# Balancing_Robot_1_1_Main.net
KiCad netlist of a schematic drawn in Altium Designer
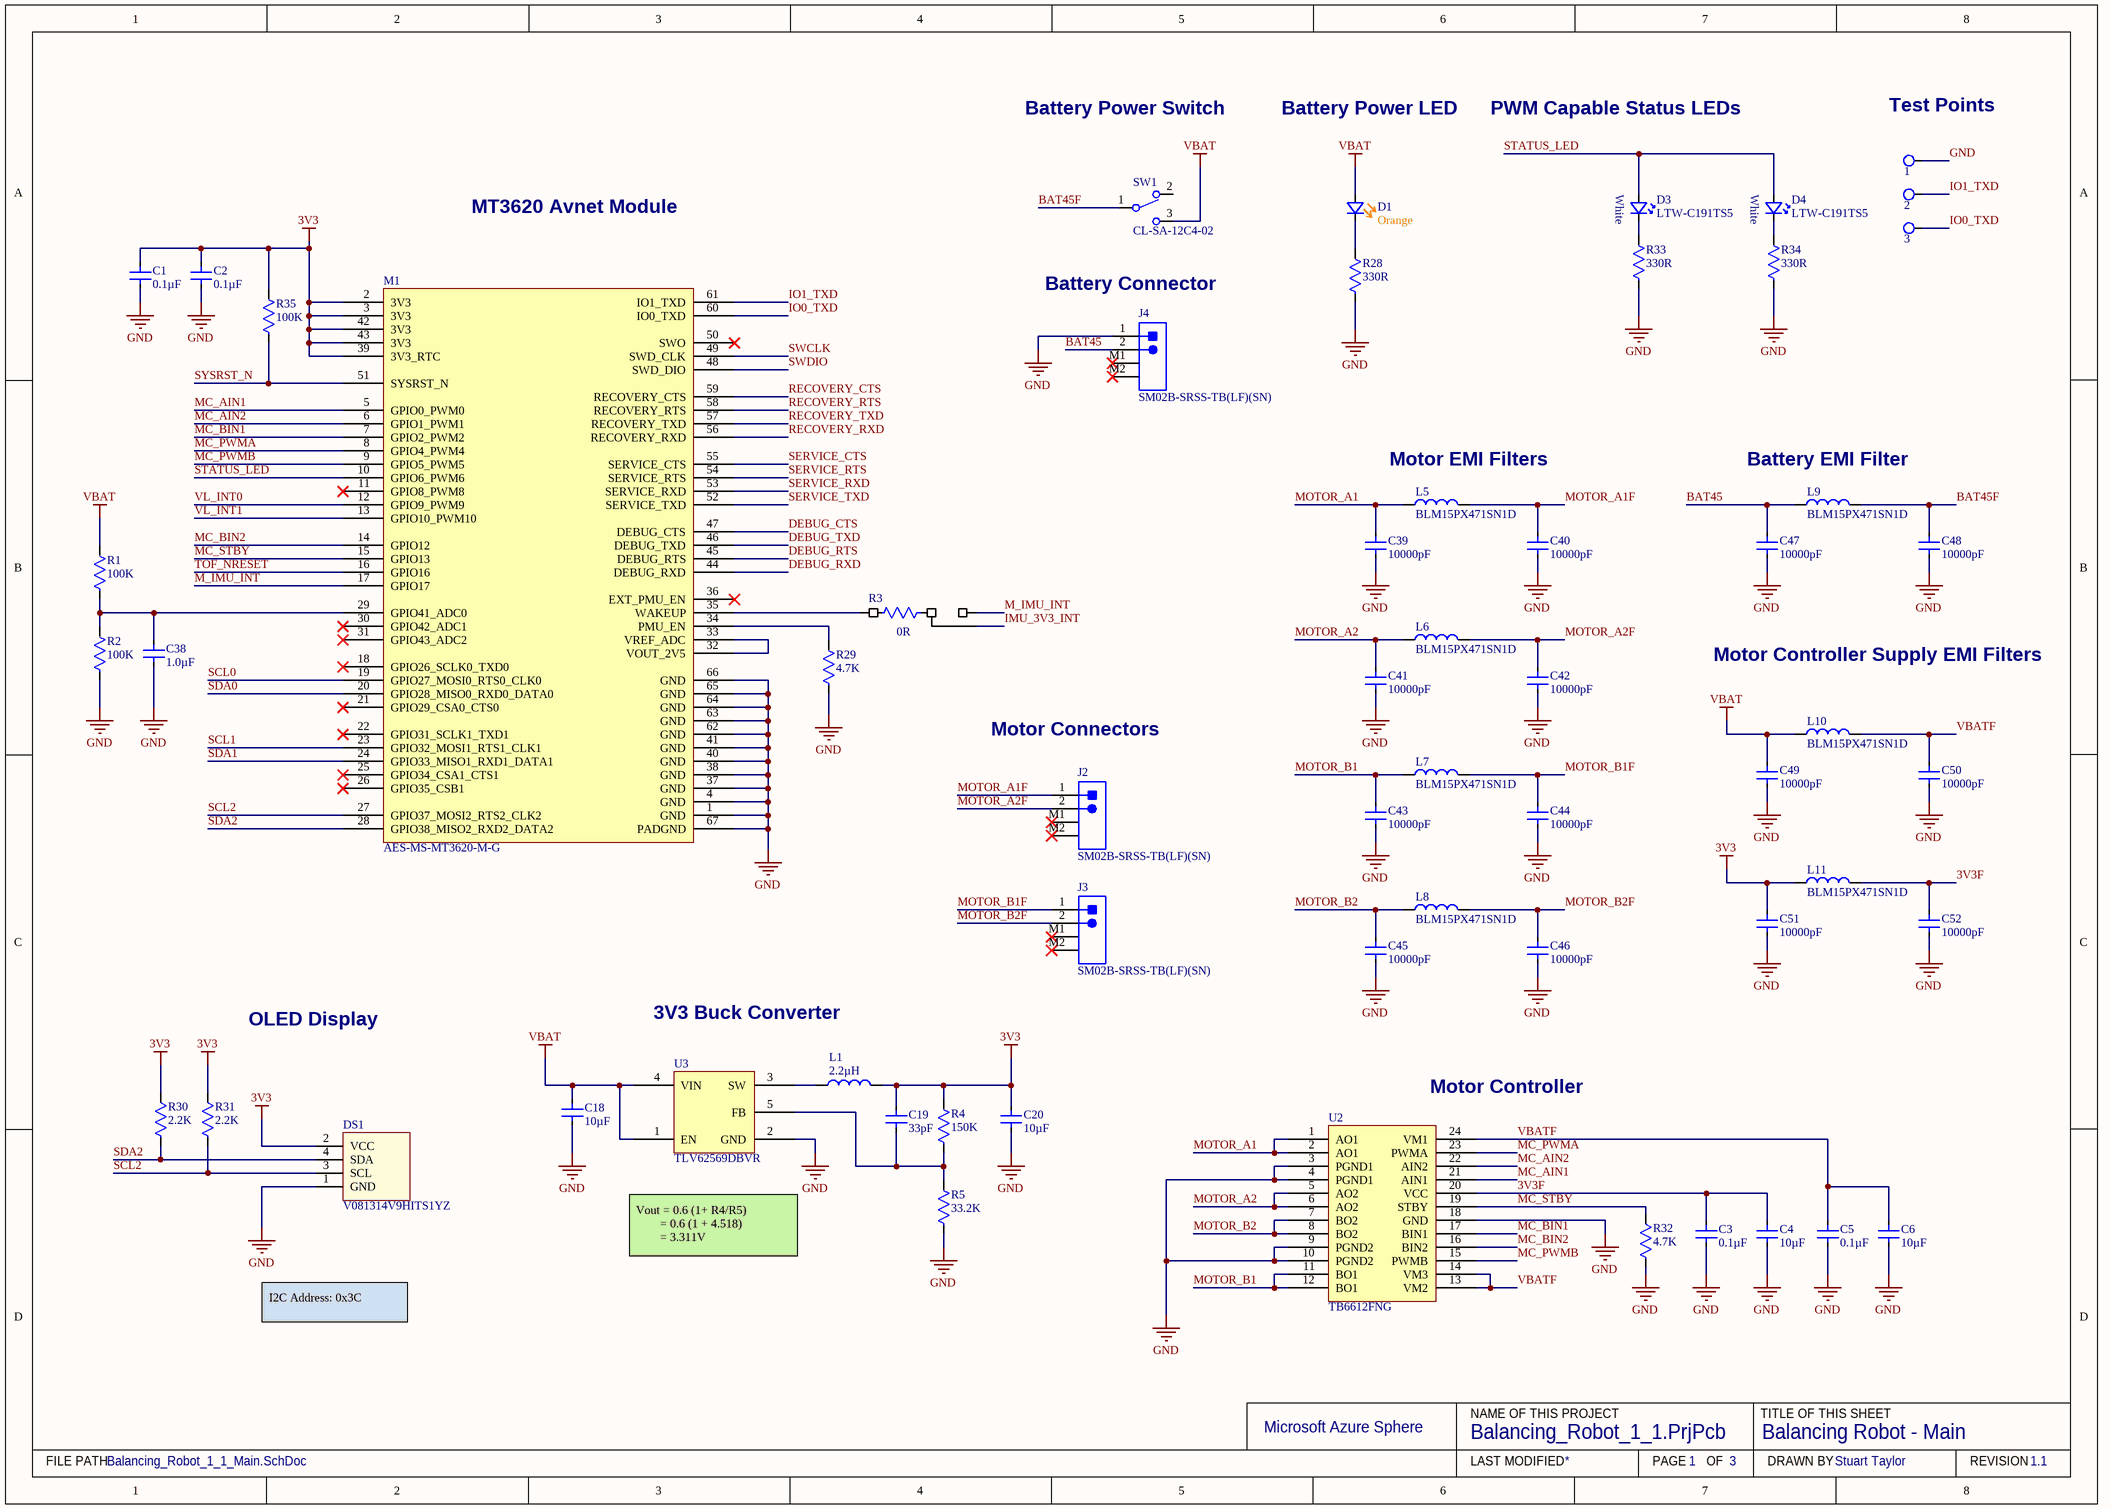
[diagram p0: Balancing_Robot_1_1_Main.SchDoc]

(export (version "E")
  (design (tool "Eeschema 10.0.6"))
  (components
    (comp (ref "1")
      (value "TestPoint")
      (footprint "Pad1.27mm")
      (description "Test Point")
      (libsource (lib "generic") (part "TestPoint"))
    )
    (comp (ref "2")
      (value "TestPoint")
      (footprint "Pad1.27mm")
      (description "Test Point")
      (libsource (lib "generic") (part "TestPoint"))
    )
    (comp (ref "3")
      (value "TestPoint")
      (footprint "Pad1.27mm")
      (description "Test Point")
      (libsource (lib "generic") (part "TestPoint"))
    )
    (comp (ref "C1")
      (value "0.1µF")
      (footprint "CAPC1005-EIA0402 0.55MM MED")
      (description "CAP CER 0.1UF 50V 10% X7R 0402")
      (fields
        (field (name "MANUFACTURER") "TDK Corporation")
        (field (name "MANUFACTURER PART NUMBER") "C1005X7R1H104K050BB")
        (field (name "CAPACITANCE") "0.1µF")
      )
      (libsource (lib "TDK_Capacitor_C_0402") (part "0.1µF 0402 X7R 50V"))
    )
    (comp (ref "C2")
      (value "0.1µF")
      (footprint "CAPC1005-EIA0402 0.55MM MED")
      (description "CAP CER 0.1UF 50V 10% X7R 0402")
      (fields
        (field (name "MANUFACTURER") "TDK Corporation")
        (field (name "MANUFACTURER PART NUMBER") "C1005X7R1H104K050BB")
        (field (name "CAPACITANCE") "0.1µF")
      )
      (libsource (lib "TDK_Capacitor_C_0402") (part "0.1µF 0402 X7R 50V"))
    )
    (comp (ref "C3")
      (value "0.1µF")
      (footprint "CAPC1005-EIA0402 0.55MM MED")
      (description "CAP CER 0.1UF 50V 10% X7R 0402")
      (fields
        (field (name "MANUFACTURER") "TDK Corporation")
        (field (name "MANUFACTURER PART NUMBER") "C1005X7R1H104K050BB")
        (field (name "CAPACITANCE") "0.1µF")
      )
      (libsource (lib "TDK_Capacitor_C_0402") (part "0.1µF 0402 X7R 50V"))
    )
    (comp (ref "C4")
      (value "10µF")
      (footprint "CAPC1005-EIA0402 0.55MM MED")
      (description "CAP CER 10UF 6.3V 20% X5R 0402")
      (fields
        (field (name "MANUFACTURER") "TDK Corporation")
        (field (name "MANUFACTURER PART NUMBER") "C1005X5R0J106M050BC")
        (field (name "CAPACITANCE") "10µF")
      )
      (libsource (lib "TDK_Capacitor_C_0402") (part "10µF 0402 X5R 6.3V"))
    )
    (comp (ref "C5")
      (value "0.1µF")
      (footprint "CAPC1005-EIA0402 0.55MM MED")
      (description "CAP CER 0.1UF 50V 10% X7R 0402")
      (fields
        (field (name "MANUFACTURER") "TDK Corporation")
        (field (name "MANUFACTURER PART NUMBER") "C1005X7R1H104K050BB")
        (field (name "CAPACITANCE") "0.1µF")
      )
      (libsource (lib "TDK_Capacitor_C_0402") (part "0.1µF 0402 X7R 50V"))
    )
    (comp (ref "C6")
      (value "10µF")
      (footprint "CAPC1005-EIA0402 0.55MM MED")
      (description "CAP CER 10UF 6.3V 20% X5R 0402")
      (fields
        (field (name "MANUFACTURER") "TDK Corporation")
        (field (name "MANUFACTURER PART NUMBER") "C1005X5R0J106M050BC")
        (field (name "CAPACITANCE") "10µF")
      )
      (libsource (lib "TDK_Capacitor_C_0402") (part "10µF 0402 X5R 6.3V"))
    )
    (comp (ref "C18")
      (value "10µF")
      (footprint "CAPC1608-EIA0603-1MM-MED")
      (description "CAP CER 10UF 25V 20% X5R 0603")
      (fields
        (field (name "MANUFACTURER") "TDK Corporation")
        (field (name "MANUFACTURER PART NUMBER") "C1608X5R1E106M080AC")
        (field (name "CAPACITANCE") "10µF")
      )
      (libsource (lib "TDK-Capacitor_C_0603") (part "10µF 0603 X5R 25V"))
    )
    (comp (ref "C19")
      (value "33pF")
      (footprint "CAPC1005-EIA0402 0.55MM MED")
      (description "CAP CER 33PF 50V 5% NP0 0402")
      (fields
        (field (name "MANUFACTURER") "TDK Corporation")
        (field (name "MANUFACTURER PART NUMBER") "C1005C0G1H330J050BA")
        (field (name "CAPACITANCE") "33pF")
      )
      (libsource (lib "TDK_Capacitor_C_0402") (part "33pF 0402 C0G, NP0 50V"))
    )
    (comp (ref "C20")
      (value "10µF")
      (footprint "CAPC1005-EIA0402 0.55MM MED")
      (description "CAP CER 10UF 6.3V 20% X5R 0402")
      (fields
        (field (name "MANUFACTURER") "TDK Corporation")
        (field (name "MANUFACTURER PART NUMBER") "C1005X5R0J106M050BC")
        (field (name "CAPACITANCE") "10µF")
      )
      (libsource (lib "TDK_Capacitor_C_0402") (part "10µF 0402 X5R 6.3V"))
    )
    (comp (ref "C38")
      (value "C1005X5R1V105K050BC")
      (footprint "CAPC1005-EIA0402 0.55MM MED")
      (description "CAP CER 1UF 35V 10% X5R 0402")
      (fields
        (field (name "MANUFACTURER") "TDK Corporation")
        (field (name "TOLERANCE") "±10%")
        (field (name "CAPACITANCE") "1.0µF")
      )
      (libsource (lib "TDK_Capacitor_C_0402") (part "1.0µF 0402 X5R 35V"))
    )
    (comp (ref "C39")
      (value "C1005X7R1H103K050BB")
      (footprint "CAPC1005-EIA0402 0.55MM MED")
      (description "CAP CER 10000PF 50V 10% X7R 0402")
      (fields
        (field (name "MANUFACTURER") "TDK Corporation")
        (field (name "TOLERANCE") "±10%")
        (field (name "CAPACITANCE") "10000pF")
      )
      (libsource (lib "TDK_Capacitor_C_0402") (part "10000pF 0402 X7R 50V"))
    )
    (comp (ref "C40")
      (value "C1005X7R1H103K050BB")
      (footprint "CAPC1005-EIA0402 0.55MM MED")
      (description "CAP CER 10000PF 50V 10% X7R 0402")
      (fields
        (field (name "MANUFACTURER") "TDK Corporation")
        (field (name "TOLERANCE") "±10%")
        (field (name "CAPACITANCE") "10000pF")
      )
      (libsource (lib "TDK_Capacitor_C_0402") (part "10000pF 0402 X7R 50V"))
    )
    (comp (ref "C41")
      (value "C1005X7R1H103K050BB")
      (footprint "CAPC1005-EIA0402 0.55MM MED")
      (description "CAP CER 10000PF 50V 10% X7R 0402")
      (fields
        (field (name "MANUFACTURER") "TDK Corporation")
        (field (name "TOLERANCE") "±10%")
        (field (name "CAPACITANCE") "10000pF")
      )
      (libsource (lib "TDK_Capacitor_C_0402") (part "10000pF 0402 X7R 50V"))
    )
    (comp (ref "C42")
      (value "C1005X7R1H103K050BB")
      (footprint "CAPC1005-EIA0402 0.55MM MED")
      (description "CAP CER 10000PF 50V 10% X7R 0402")
      (fields
        (field (name "MANUFACTURER") "TDK Corporation")
        (field (name "TOLERANCE") "±10%")
        (field (name "CAPACITANCE") "10000pF")
      )
      (libsource (lib "TDK_Capacitor_C_0402") (part "10000pF 0402 X7R 50V"))
    )
    (comp (ref "C43")
      (value "C1005X7R1H103K050BB")
      (footprint "CAPC1005-EIA0402 0.55MM MED")
      (description "CAP CER 10000PF 50V 10% X7R 0402")
      (fields
        (field (name "MANUFACTURER") "TDK Corporation")
        (field (name "TOLERANCE") "±10%")
        (field (name "CAPACITANCE") "10000pF")
      )
      (libsource (lib "TDK_Capacitor_C_0402") (part "10000pF 0402 X7R 50V"))
    )
    (comp (ref "C44")
      (value "C1005X7R1H103K050BB")
      (footprint "CAPC1005-EIA0402 0.55MM MED")
      (description "CAP CER 10000PF 50V 10% X7R 0402")
      (fields
        (field (name "MANUFACTURER") "TDK Corporation")
        (field (name "TOLERANCE") "±10%")
        (field (name "CAPACITANCE") "10000pF")
      )
      (libsource (lib "TDK_Capacitor_C_0402") (part "10000pF 0402 X7R 50V"))
    )
    (comp (ref "C45")
      (value "C1005X7R1H103K050BB")
      (footprint "CAPC1005-EIA0402 0.55MM MED")
      (description "CAP CER 10000PF 50V 10% X7R 0402")
      (fields
        (field (name "MANUFACTURER") "TDK Corporation")
        (field (name "TOLERANCE") "±10%")
        (field (name "CAPACITANCE") "10000pF")
      )
      (libsource (lib "TDK_Capacitor_C_0402") (part "10000pF 0402 X7R 50V"))
    )
    (comp (ref "C46")
      (value "C1005X7R1H103K050BB")
      (footprint "CAPC1005-EIA0402 0.55MM MED")
      (description "CAP CER 10000PF 50V 10% X7R 0402")
      (fields
        (field (name "MANUFACTURER") "TDK Corporation")
        (field (name "TOLERANCE") "±10%")
        (field (name "CAPACITANCE") "10000pF")
      )
      (libsource (lib "TDK_Capacitor_C_0402") (part "10000pF 0402 X7R 50V"))
    )
    (comp (ref "C47")
      (value "C1005X7R1H103K050BB")
      (footprint "CAPC1005-EIA0402 0.55MM MED")
      (description "CAP CER 10000PF 50V 10% X7R 0402")
      (fields
        (field (name "MANUFACTURER") "TDK Corporation")
        (field (name "TOLERANCE") "±10%")
        (field (name "CAPACITANCE") "10000pF")
      )
      (libsource (lib "TDK_Capacitor_C_0402") (part "10000pF 0402 X7R 50V"))
    )
    (comp (ref "C48")
      (value "C1005X7R1H103K050BB")
      (footprint "CAPC1005-EIA0402 0.55MM MED")
      (description "CAP CER 10000PF 50V 10% X7R 0402")
      (fields
        (field (name "MANUFACTURER") "TDK Corporation")
        (field (name "TOLERANCE") "±10%")
        (field (name "CAPACITANCE") "10000pF")
      )
      (libsource (lib "TDK_Capacitor_C_0402") (part "10000pF 0402 X7R 50V"))
    )
    (comp (ref "C49")
      (value "C1005X7R1H103K050BB")
      (footprint "CAPC1005-EIA0402 0.55MM MED")
      (description "CAP CER 10000PF 50V 10% X7R 0402")
      (fields
        (field (name "MANUFACTURER") "TDK Corporation")
        (field (name "TOLERANCE") "±10%")
        (field (name "CAPACITANCE") "10000pF")
      )
      (libsource (lib "TDK_Capacitor_C_0402") (part "10000pF 0402 X7R 50V"))
    )
    (comp (ref "C50")
      (value "C1005X7R1H103K050BB")
      (footprint "CAPC1005-EIA0402 0.55MM MED")
      (description "CAP CER 10000PF 50V 10% X7R 0402")
      (fields
        (field (name "MANUFACTURER") "TDK Corporation")
        (field (name "TOLERANCE") "±10%")
        (field (name "CAPACITANCE") "10000pF")
      )
      (libsource (lib "TDK_Capacitor_C_0402") (part "10000pF 0402 X7R 50V"))
    )
    (comp (ref "C51")
      (value "C1005X7R1H103K050BB")
      (footprint "CAPC1005-EIA0402 0.55MM MED")
      (description "CAP CER 10000PF 50V 10% X7R 0402")
      (fields
        (field (name "MANUFACTURER") "TDK Corporation")
        (field (name "TOLERANCE") "±10%")
        (field (name "CAPACITANCE") "10000pF")
      )
      (libsource (lib "TDK_Capacitor_C_0402") (part "10000pF 0402 X7R 50V"))
    )
    (comp (ref "C52")
      (value "C1005X7R1H103K050BB")
      (footprint "CAPC1005-EIA0402 0.55MM MED")
      (description "CAP CER 10000PF 50V 10% X7R 0402")
      (fields
        (field (name "MANUFACTURER") "TDK Corporation")
        (field (name "TOLERANCE") "±10%")
        (field (name "CAPACITANCE") "10000pF")
      )
      (libsource (lib "TDK_Capacitor_C_0402") (part "10000pF 0402 X7R 50V"))
    )
    (comp (ref "D1")
      (value "SML-D12D")
      (footprint "Rohm SML-D12 Orange")
      (description "1.6 x 0.8 x 0.55mm (0603) LED 605nm Orange")
      (fields
        (field (name "MANUFACTURER") "Rohm Semiconductor")
        (field (name "MANUFACTURER PART NUMBER") "SML-D12D8WT86")
        (field (name "COLOUR") "Orange")
      )
      (libsource (lib "Rohm") (part "SML-D12D"))
    )
    (comp (ref "D3")
      (value "LTW-C191TS5")
      (footprint "LTW-C191TS5")
      (description "LED Uni-Color White 2-Pin Chip LED T/R")
      (fields (field (name "MANUFACTURER") "Vishay Lite-On"))
      (libsource (lib "Lite-On") (part "LTW-C191TS5"))
    )
    (comp (ref "D4")
      (value "LTW-C191TS5")
      (footprint "LTW-C191TS5")
      (description "LED Uni-Color White 2-Pin Chip LED T/R")
      (fields (field (name "MANUFACTURER") "Vishay Lite-On"))
      (libsource (lib "Lite-On") (part "LTW-C191TS5"))
    )
    (comp (ref "DS1")
      (value "V081314V9HITS1YZ")
      (footprint "Long_Display")
      (libsource (lib "MakerHawk") (part "V081314V9HITS1YZ"))
    )
    (comp (ref "J2")
      (value "SM02B-SRSS-TB(LF)(SN)")
      (footprint "SM02B-SRSS-TB")
      (description "Conn Shrouded Header HDR 2 POS 1mm Solder RA SMD T/R")
      (fields (field (name "MANUFACTURER") "JST"))
      (libsource (lib "JST") (part "SM02B-SRSS-TB(LF)(SN)"))
    )
    (comp (ref "J3")
      (value "SM02B-SRSS-TB(LF)(SN)")
      (footprint "SM02B-SRSS-TB")
      (description "Conn Shrouded Header HDR 2 POS 1mm Solder RA SMD T/R")
      (fields (field (name "MANUFACTURER") "JST"))
      (libsource (lib "JST") (part "SM02B-SRSS-TB(LF)(SN)"))
    )
    (comp (ref "J4")
      (value "SM02B-SRSS-TB(LF)(SN)")
      (footprint "SM02B-SRSS-TB")
      (description "Conn Shrouded Header HDR 2 POS 1mm Solder RA SMD T/R")
      (fields (field (name "MANUFACTURER") "JST"))
      (libsource (lib "JST") (part "SM02B-SRSS-TB(LF)(SN)"))
    )
    (comp (ref "L1")
      (value "2.2µH")
      (footprint "NR3015T2R2M")
      (description "FIXED IND 2.2UH 1.5A 72 MOHM SMD")
      (fields
        (field (name "MANUFACTURER") "Taiyo Yuden")
        (field (name "MANUFACTURER PART NUMBER") "NR3015T2R2M")
      )
      (libsource (lib "TaiyoYuden ") (part "NR3015T2R2M"))
    )
    (comp (ref "L5")
      (value "BLM15PX471SN1D")
      (footprint "Generic Ferrite 0402")
      (description "Murata")
      (fields (field (name "TOLERANCE") "25%"))
      (libsource (lib "Murata") (part "BLM15PX471SN1D"))
    )
    (comp (ref "L6")
      (value "BLM15PX471SN1D")
      (footprint "Generic Ferrite 0402")
      (description "Murata")
      (fields (field (name "TOLERANCE") "25%"))
      (libsource (lib "Murata") (part "BLM15PX471SN1D"))
    )
    (comp (ref "L7")
      (value "BLM15PX471SN1D")
      (footprint "Generic Ferrite 0402")
      (description "Murata")
      (fields (field (name "TOLERANCE") "25%"))
      (libsource (lib "Murata") (part "BLM15PX471SN1D"))
    )
    (comp (ref "L8")
      (value "BLM15PX471SN1D")
      (footprint "Generic Ferrite 0402")
      (description "Murata")
      (fields (field (name "TOLERANCE") "25%"))
      (libsource (lib "Murata") (part "BLM15PX471SN1D"))
    )
    (comp (ref "L9")
      (value "BLM15PX471SN1D")
      (footprint "Generic Ferrite 0402")
      (description "Murata")
      (fields (field (name "TOLERANCE") "25%"))
      (libsource (lib "Murata") (part "BLM15PX471SN1D"))
    )
    (comp (ref "L10")
      (value "BLM15PX471SN1D")
      (footprint "Generic Ferrite 0402")
      (description "Murata")
      (fields (field (name "TOLERANCE") "25%"))
      (libsource (lib "Murata") (part "BLM15PX471SN1D"))
    )
    (comp (ref "L11")
      (value "BLM15PX471SN1D")
      (footprint "Generic Ferrite 0402")
      (description "Murata")
      (fields (field (name "TOLERANCE") "25%"))
      (libsource (lib "Murata") (part "BLM15PX471SN1D"))
    )
    (comp (ref "M1")
      (value "AES-MS-MT3620-M-G")
      (footprint "AES-MS-MT3620-M-G")
      (libsource (lib "Avnet") (part "AES-MS-MT3620-M-G (SAT)"))
    )
    (comp (ref "R1")
      (value "100K")
      (footprint "RES 0402 MEDIUM DENSITY")
      (description "RES 100K OHM 1/10W 1% 0402 SMD")
      (fields
        (field (name "MANUFACTURER") "Panasonic Electronic Components")
        (field (name "MANUFACTURER PART NUMBER") "ERJ-2RKF1003X")
        (field (name "RESISTANCE (OHMS)") "100K")
      )
      (libsource (lib "Panasonic_Resistor_ERJ2R") (part "100K"))
    )
    (comp (ref "R2")
      (value "100K")
      (footprint "RES 0402 MEDIUM DENSITY")
      (description "RES 100K OHM 1/10W 1% 0402 SMD")
      (fields
        (field (name "MANUFACTURER") "Panasonic Electronic Components")
        (field (name "MANUFACTURER PART NUMBER") "ERJ-2RKF1003X")
        (field (name "RESISTANCE (OHMS)") "100K")
      )
      (libsource (lib "Panasonic_Resistor_ERJ2R") (part "100K"))
    )
    (comp (ref "R3")
      (value "0R")
      (footprint "THREE-WAY-0402-NO-SHORT")
      (description "RES SMD 0.0OHM JUMPER 1/10W 0402")
      (fields
        (field (name "MANUFACTURER") "Panasonic Electronic Components")
        (field (name "MANUFACTURER PART NUMBER") "ERJ-2GE0R00X")
      )
      (libsource (lib "generic-res") (part "THREE-WAY-0R-0402-NO-SHORT"))
    )
    (comp (ref "R4")
      (value "150K")
      (footprint "RES 0402 MEDIUM DENSITY")
      (description "RES 150K OHM 1/10W 1% 0402 SMD")
      (fields
        (field (name "MANUFACTURER") "Panasonic Electronic Components")
        (field (name "MANUFACTURER PART NUMBER") "ERJ-2RKF1503X")
        (field (name "RESISTANCE (OHMS)") "150K")
      )
      (libsource (lib "Panasonic_Resistor_ERJ2R") (part "150K"))
    )
    (comp (ref "R5")
      (value "33.2K")
      (footprint "RES 0402 MEDIUM DENSITY")
      (description "RES 33.2K OHM 1/10W 1% 0402 SMD")
      (fields
        (field (name "MANUFACTURER") "Panasonic Electronic Components")
        (field (name "MANUFACTURER PART NUMBER") "ERJ-2RKF3322X")
        (field (name "RESISTANCE (OHMS)") "33.2K")
      )
      (libsource (lib "Panasonic_Resistor_ERJ2R") (part "33.2K"))
    )
    (comp (ref "R28")
      (value "330R")
      (footprint "RES 0402 MEDIUM DENSITY")
      (description "RES 330 OHM 1/10W 1% 0402 SMD")
      (fields
        (field (name "MANUFACTURER") "Panasonic Electronic Components")
        (field (name "MANUFACTURER PART NUMBER") "ERJ-2RKF3300X")
        (field (name "RESISTANCE (OHMS)") "330R")
      )
      (libsource (lib "Panasonic_Resistor_ERJ2R") (part "330R"))
    )
    (comp (ref "R29")
      (value "4.7K")
      (footprint "RES 0402 MEDIUM DENSITY")
      (description "RES 4.7K OHM 1/10W 1% 0402 SMD")
      (fields
        (field (name "MANUFACTURER") "Panasonic Electronic Components")
        (field (name "MANUFACTURER PART NUMBER") "ERJ-2RKF4701X")
        (field (name "RESISTANCE (OHMS)") "4.7K")
      )
      (libsource (lib "Panasonic_Resistor_ERJ2R") (part "4.7K"))
    )
    (comp (ref "R30")
      (value "2.2K")
      (footprint "RES 0402 MEDIUM DENSITY")
      (description "RES 2.2K OHM 1/10W 1% 0402 SMD")
      (fields
        (field (name "MANUFACTURER") "Panasonic Electronic Components")
        (field (name "MANUFACTURER PART NUMBER") "ERJ-2RKF2201X")
        (field (name "RESISTANCE (OHMS)") "2.2K")
      )
      (libsource (lib "Panasonic_Resistor_ERJ2R") (part "2.2K"))
    )
    (comp (ref "R31")
      (value "2.2K")
      (footprint "RES 0402 MEDIUM DENSITY")
      (description "RES 2.2K OHM 1/10W 1% 0402 SMD")
      (fields
        (field (name "MANUFACTURER") "Panasonic Electronic Components")
        (field (name "MANUFACTURER PART NUMBER") "ERJ-2RKF2201X")
        (field (name "RESISTANCE (OHMS)") "2.2K")
      )
      (libsource (lib "Panasonic_Resistor_ERJ2R") (part "2.2K"))
    )
    (comp (ref "R32")
      (value "4.7K")
      (footprint "RES 0402 MEDIUM DENSITY")
      (description "RES 4.7K OHM 1/10W 1% 0402 SMD")
      (fields
        (field (name "MANUFACTURER") "Panasonic Electronic Components")
        (field (name "MANUFACTURER PART NUMBER") "ERJ-2RKF4701X")
        (field (name "RESISTANCE (OHMS)") "4.7K")
      )
      (libsource (lib "Panasonic_Resistor_ERJ2R") (part "4.7K"))
    )
    (comp (ref "R33")
      (value "330R")
      (footprint "RES 0402 MEDIUM DENSITY")
      (description "RES 330 OHM 1/10W 1% 0402 SMD")
      (fields
        (field (name "MANUFACTURER") "Panasonic Electronic Components")
        (field (name "MANUFACTURER PART NUMBER") "ERJ-2RKF3300X")
        (field (name "RESISTANCE (OHMS)") "330R")
      )
      (libsource (lib "Panasonic_Resistor_ERJ2R") (part "330R"))
    )
    (comp (ref "R34")
      (value "330R")
      (footprint "RES 0402 MEDIUM DENSITY")
      (description "RES 330 OHM 1/10W 1% 0402 SMD")
      (fields
        (field (name "MANUFACTURER") "Panasonic Electronic Components")
        (field (name "MANUFACTURER PART NUMBER") "ERJ-2RKF3300X")
        (field (name "RESISTANCE (OHMS)") "330R")
      )
      (libsource (lib "Panasonic_Resistor_ERJ2R") (part "330R"))
    )
    (comp (ref "R35")
      (value "100K")
      (footprint "RES 0402 MEDIUM DENSITY")
      (description "RES 100K OHM 1/10W 1% 0402 SMD")
      (fields
        (field (name "MANUFACTURER") "Panasonic Electronic Components")
        (field (name "MANUFACTURER PART NUMBER") "ERJ-2RKF1003X")
        (field (name "RESISTANCE (OHMS)") "100K")
      )
      (libsource (lib "Panasonic_Resistor_ERJ2R") (part "100K"))
    )
    (comp (ref "SW1")
      (value "CL-SA-12C4-02")
      (footprint "CL-SA-12C4-02")
      (description "SWITCH SLIDE SPDT 500MA 12V")
      (fields (field (name "MANUFACTURER") "Nidec Copal"))
      (libsource (lib "Copal") (part "CL-SA-12C4-02"))
    )
    (comp (ref "U2")
      (value "TB6612FNG")
      (footprint "TB6612FNG")
      (description "DC Motor Driver 3V 24-Pin SSOP T/R")
      (fields
        (field (name "MANUFACTURER") "Toshiba")
        (field (name "MANUFACTURER PART NUMBER") "TB6612FNG,C,8,EL")
      )
      (libsource (lib "Toshiba") (part "TB6612FNG"))
    )
    (comp (ref "U3")
      (value "TLV62569DBVR")
      (footprint "TI-SOT23-6")
      (description "Variable voltage buck converter")
      (fields (field (name "MANUFACTURER") "Texas Instruments"))
      (libsource (lib "TexasInstruments") (part "TLV62569DBVR"))
    )
  )
  (nets
    (net (code "1") (name "/3V3F") (class "Default")
      (node (ref "C3") (pin "2") (pinfunction "2_2") (pintype "passive"))
      (node (ref "C4") (pin "2") (pinfunction "2_2") (pintype "passive"))
      (node (ref "C52") (pin "2") (pinfunction "2_2") (pintype "passive"))
      (node (ref "L11") (pin "2") (pinfunction "2_2") (pintype "passive"))
      (node (ref "U2") (pin "20") (pinfunction "VCC_20") (pintype "passive"))
    )
    (net (code "2") (name "/BAT45") (class "Default")
      (node (ref "C47") (pin "2") (pinfunction "2_2") (pintype "passive"))
      (node (ref "J4") (pin "2") (pinfunction "2_2") (pintype "passive"))
      (node (ref "L9") (pin "1") (pinfunction "1_1") (pintype "passive"))
    )
    (net (code "3") (name "/BAT45F") (class "Default")
      (node (ref "C48") (pin "2") (pinfunction "2_2") (pintype "passive"))
      (node (ref "L9") (pin "2") (pinfunction "2_2") (pintype "passive"))
      (node (ref "SW1") (pin "1") (pinfunction "1_1") (pintype "passive"))
    )
    (net (code "4") (name "/DEBUG_CTS") (class "Default")
      (node (ref "M1") (pin "47") (pinfunction "DEBUG_CTS_47") (pintype "passive"))
    )
    (net (code "5") (name "/DEBUG_RTS") (class "Default")
      (node (ref "M1") (pin "45") (pinfunction "DEBUG_RTS_45") (pintype "passive"))
    )
    (net (code "6") (name "/DEBUG_RXD") (class "Default")
      (node (ref "M1") (pin "44") (pinfunction "DEBUG_RXD_44") (pintype "passive"))
    )
    (net (code "7") (name "/DEBUG_TXD") (class "Default")
      (node (ref "M1") (pin "46") (pinfunction "DEBUG_TXD_46") (pintype "passive"))
    )
    (net (code "8") (name "/IMU_3V3_INT") (class "Default")
      (node (ref "R3") (pin "2") (pinfunction "2_2") (pintype "passive"))
    )
    (net (code "9") (name "/IO0_TXD") (class "Default")
      (node (ref "3") (pin "1") (pinfunction "1_1") (pintype "passive"))
      (node (ref "M1") (pin "60") (pinfunction "IO0_TXD_60") (pintype "passive"))
    )
    (net (code "10") (name "/IO1_TXD") (class "Default")
      (node (ref "2") (pin "1") (pinfunction "1_1") (pintype "passive"))
      (node (ref "M1") (pin "61") (pinfunction "IO1_TXD_61") (pintype "passive"))
    )
    (net (code "11") (name "/MC_AIN1") (class "Default")
      (node (ref "M1") (pin "5") (pinfunction "GPIO0_PWM0_5") (pintype "passive"))
      (node (ref "U2") (pin "21") (pinfunction "AIN1_21") (pintype "passive"))
    )
    (net (code "12") (name "/MC_AIN2") (class "Default")
      (node (ref "M1") (pin "6") (pinfunction "GPIO1_PWM1_6") (pintype "passive"))
      (node (ref "U2") (pin "22") (pinfunction "AIN2_22") (pintype "passive"))
    )
    (net (code "13") (name "/MC_BIN1") (class "Default")
      (node (ref "M1") (pin "7") (pinfunction "GPIO2_PWM2_7") (pintype "passive"))
      (node (ref "U2") (pin "17") (pinfunction "BIN1_17") (pintype "passive"))
    )
    (net (code "14") (name "/MC_BIN2") (class "Default")
      (node (ref "M1") (pin "14") (pinfunction "GPIO12_14") (pintype "passive"))
      (node (ref "U2") (pin "16") (pinfunction "BIN2_16") (pintype "passive"))
    )
    (net (code "15") (name "/MC_PWMA") (class "Default")
      (node (ref "M1") (pin "8") (pinfunction "GPIO4_PWM4_8") (pintype "passive"))
      (node (ref "U2") (pin "23") (pinfunction "PWMA_23") (pintype "passive"))
    )
    (net (code "16") (name "/MC_PWMB") (class "Default")
      (node (ref "M1") (pin "9") (pinfunction "GPIO5_PWM5_9") (pintype "passive"))
      (node (ref "U2") (pin "15") (pinfunction "PWMB_15") (pintype "passive"))
    )
    (net (code "17") (name "/MC_STBY") (class "Default")
      (node (ref "M1") (pin "15") (pinfunction "GPIO13_15") (pintype "passive"))
      (node (ref "R32") (pin "1") (pinfunction "1_1") (pintype "passive"))
      (node (ref "U2") (pin "19") (pinfunction "STBY_19") (pintype "passive"))
    )
    (net (code "18") (name "/MOTOR_A1") (class "Default")
      (node (ref "C39") (pin "2") (pinfunction "2_2") (pintype "passive"))
      (node (ref "L5") (pin "1") (pinfunction "1_1") (pintype "passive"))
      (node (ref "U2") (pin "1") (pinfunction "AO1_1") (pintype "passive"))
      (node (ref "U2") (pin "2") (pinfunction "AO1_2") (pintype "passive"))
    )
    (net (code "19") (name "/MOTOR_A1F") (class "Default")
      (node (ref "C40") (pin "2") (pinfunction "2_2") (pintype "passive"))
      (node (ref "J2") (pin "1") (pinfunction "1_1") (pintype "passive"))
      (node (ref "L5") (pin "2") (pinfunction "2_2") (pintype "passive"))
    )
    (net (code "20") (name "/MOTOR_A2") (class "Default")
      (node (ref "C41") (pin "2") (pinfunction "2_2") (pintype "passive"))
      (node (ref "L6") (pin "1") (pinfunction "1_1") (pintype "passive"))
      (node (ref "U2") (pin "5") (pinfunction "AO2_5") (pintype "passive"))
      (node (ref "U2") (pin "6") (pinfunction "AO2_6") (pintype "passive"))
    )
    (net (code "21") (name "/MOTOR_A2F") (class "Default")
      (node (ref "C42") (pin "2") (pinfunction "2_2") (pintype "passive"))
      (node (ref "J2") (pin "2") (pinfunction "2_2") (pintype "passive"))
      (node (ref "L6") (pin "2") (pinfunction "2_2") (pintype "passive"))
    )
    (net (code "22") (name "/MOTOR_B1") (class "Default")
      (node (ref "C43") (pin "2") (pinfunction "2_2") (pintype "passive"))
      (node (ref "L7") (pin "1") (pinfunction "1_1") (pintype "passive"))
      (node (ref "U2") (pin "11") (pinfunction "BO1_11") (pintype "passive"))
      (node (ref "U2") (pin "12") (pinfunction "BO1_12") (pintype "passive"))
    )
    (net (code "23") (name "/MOTOR_B1F") (class "Default")
      (node (ref "C44") (pin "2") (pinfunction "2_2") (pintype "passive"))
      (node (ref "J3") (pin "1") (pinfunction "1_1") (pintype "passive"))
      (node (ref "L7") (pin "2") (pinfunction "2_2") (pintype "passive"))
    )
    (net (code "24") (name "/MOTOR_B2") (class "Default")
      (node (ref "C45") (pin "2") (pinfunction "2_2") (pintype "passive"))
      (node (ref "L8") (pin "1") (pinfunction "1_1") (pintype "passive"))
      (node (ref "U2") (pin "7") (pinfunction "BO2_7") (pintype "passive"))
      (node (ref "U2") (pin "8") (pinfunction "BO2_8") (pintype "passive"))
    )
    (net (code "25") (name "/MOTOR_B2F") (class "Default")
      (node (ref "C46") (pin "2") (pinfunction "2_2") (pintype "passive"))
      (node (ref "J3") (pin "2") (pinfunction "2_2") (pintype "passive"))
      (node (ref "L8") (pin "2") (pinfunction "2_2") (pintype "passive"))
    )
    (net (code "26") (name "/M_IMU_INT") (class "Default")
      (node (ref "M1") (pin "17") (pinfunction "GPIO17_17") (pintype "passive"))
      (node (ref "R3") (pin "3") (pinfunction "3_3") (pintype "passive"))
    )
    (net (code "27") (name "/RECOVERY_CTS") (class "Default")
      (node (ref "M1") (pin "59") (pinfunction "RECOVERY_CTS_59") (pintype "passive"))
    )
    (net (code "28") (name "/RECOVERY_RTS") (class "Default")
      (node (ref "M1") (pin "58") (pinfunction "RECOVERY_RTS_58") (pintype "passive"))
    )
    (net (code "29") (name "/RECOVERY_RXD") (class "Default")
      (node (ref "M1") (pin "56") (pinfunction "RECOVERY_RXD_56") (pintype "passive"))
    )
    (net (code "30") (name "/RECOVERY_TXD") (class "Default")
      (node (ref "M1") (pin "57") (pinfunction "RECOVERY_TXD_57") (pintype "passive"))
    )
    (net (code "31") (name "/SCL0") (class "Default")
      (node (ref "M1") (pin "19") (pinfunction "GPIO27_MOSI0_RTS0_CLK0_19") (pintype "passive"))
    )
    (net (code "32") (name "/SCL1") (class "Default")
      (node (ref "M1") (pin "23") (pinfunction "GPIO32_MOSI1_RTS1_CLK1_23") (pintype "passive"))
    )
    (net (code "33") (name "/SCL2") (class "Default")
      (node (ref "DS1") (pin "3") (pinfunction "SCL_3") (pintype "passive"))
      (node (ref "M1") (pin "27") (pinfunction "GPIO37_MOSI2_RTS2_CLK2_27") (pintype "passive"))
      (node (ref "R31") (pin "2") (pinfunction "2_2") (pintype "passive"))
    )
    (net (code "34") (name "/SDA0") (class "Default")
      (node (ref "M1") (pin "20") (pinfunction "GPIO28_MISO0_RXD0_DATA0_20") (pintype "passive"))
    )
    (net (code "35") (name "/SDA1") (class "Default")
      (node (ref "M1") (pin "24") (pinfunction "GPIO33_MISO1_RXD1_DATA1_24") (pintype "passive"))
    )
    (net (code "36") (name "/SDA2") (class "Default")
      (node (ref "DS1") (pin "4") (pinfunction "SDA_4") (pintype "passive"))
      (node (ref "M1") (pin "28") (pinfunction "GPIO38_MISO2_RXD2_DATA2_28") (pintype "passive"))
      (node (ref "R30") (pin "2") (pinfunction "2_2") (pintype "passive"))
    )
    (net (code "37") (name "/SERVICE_CTS") (class "Default")
      (node (ref "M1") (pin "55") (pinfunction "SERVICE_CTS_55") (pintype "passive"))
    )
    (net (code "38") (name "/SERVICE_RTS") (class "Default")
      (node (ref "M1") (pin "54") (pinfunction "SERVICE_RTS_54") (pintype "passive"))
    )
    (net (code "39") (name "/SERVICE_RXD") (class "Default")
      (node (ref "M1") (pin "53") (pinfunction "SERVICE_RXD_53") (pintype "passive"))
    )
    (net (code "40") (name "/SERVICE_TXD") (class "Default")
      (node (ref "M1") (pin "52") (pinfunction "SERVICE_TXD_52") (pintype "passive"))
    )
    (net (code "41") (name "/STATUS_LED") (class "Default")
      (node (ref "D3") (pin "2") (pinfunction "A_2") (pintype "passive"))
      (node (ref "D4") (pin "2") (pinfunction "A_2") (pintype "passive"))
      (node (ref "M1") (pin "10") (pinfunction "GPIO6_PWM6_10") (pintype "passive"))
    )
    (net (code "42") (name "/SWCLK") (class "Default")
      (node (ref "M1") (pin "49") (pinfunction "SWD_CLK_49") (pintype "passive"))
    )
    (net (code "43") (name "/SWDIO") (class "Default")
      (node (ref "M1") (pin "48") (pinfunction "SWD_DIO_48") (pintype "passive"))
    )
    (net (code "44") (name "/SYSRST_N") (class "Default")
      (node (ref "M1") (pin "51") (pinfunction "SYSRST_N_51") (pintype "passive"))
      (node (ref "R35") (pin "2") (pinfunction "2_2") (pintype "passive"))
    )
    (net (code "45") (name "/TOF_NRESET") (class "Default")
      (node (ref "M1") (pin "16") (pinfunction "GPIO16_16") (pintype "passive"))
    )
    (net (code "46") (name "/VBATF") (class "Default")
      (node (ref "C5") (pin "2") (pinfunction "2_2") (pintype "passive"))
      (node (ref "C50") (pin "2") (pinfunction "2_2") (pintype "passive"))
      (node (ref "C6") (pin "2") (pinfunction "2_2") (pintype "passive"))
      (node (ref "L10") (pin "2") (pinfunction "2_2") (pintype "passive"))
      (node (ref "U2") (pin "13") (pinfunction "VM2_13") (pintype "passive"))
      (node (ref "U2") (pin "14") (pinfunction "VM3_14") (pintype "passive"))
      (node (ref "U2") (pin "24") (pinfunction "VM1_24") (pintype "passive"))
    )
    (net (code "47") (name "/VL_INT0") (class "Default")
      (node (ref "M1") (pin "12") (pinfunction "GPIO9_PWM9_12") (pintype "passive"))
    )
    (net (code "48") (name "/VL_INT1") (class "Default")
      (node (ref "M1") (pin "13") (pinfunction "GPIO10_PWM10_13") (pintype "passive"))
    )
    (net (code "49") (name "3V3") (class "Default")
      (node (ref "C1") (pin "2") (pinfunction "2_2") (pintype "passive"))
      (node (ref "C19") (pin "2") (pinfunction "2_2") (pintype "passive"))
      (node (ref "C2") (pin "2") (pinfunction "2_2") (pintype "passive"))
      (node (ref "C20") (pin "2") (pinfunction "2_2") (pintype "passive"))
      (node (ref "C51") (pin "2") (pinfunction "2_2") (pintype "passive"))
      (node (ref "DS1") (pin "2") (pinfunction "VCC_2") (pintype "passive"))
      (node (ref "L1") (pin "2") (pinfunction "2_2") (pintype "passive"))
      (node (ref "L11") (pin "1") (pinfunction "1_1") (pintype "passive"))
      (node (ref "M1") (pin "2") (pinfunction "3V3_2") (pintype "passive"))
      (node (ref "M1") (pin "3") (pinfunction "3V3_3") (pintype "passive"))
      (node (ref "M1") (pin "39") (pinfunction "3V3_RTC_39") (pintype "passive"))
      (node (ref "M1") (pin "42") (pinfunction "3V3_42") (pintype "passive"))
      (node (ref "M1") (pin "43") (pinfunction "3V3_43") (pintype "passive"))
      (node (ref "R30") (pin "1") (pinfunction "1_1") (pintype "passive"))
      (node (ref "R31") (pin "1") (pinfunction "1_1") (pintype "passive"))
      (node (ref "R35") (pin "1") (pinfunction "1_1") (pintype "passive"))
      (node (ref "R4") (pin "1") (pinfunction "1_1") (pintype "passive"))
    )
    (net (code "50") (name "GND") (class "Default")
      (node (ref "1") (pin "1") (pinfunction "1_1") (pintype "passive"))
      (node (ref "C1") (pin "1") (pinfunction "1_1") (pintype "passive"))
      (node (ref "C18") (pin "1") (pinfunction "1_1") (pintype "passive"))
      (node (ref "C2") (pin "1") (pinfunction "1_1") (pintype "passive"))
      (node (ref "C20") (pin "1") (pinfunction "1_1") (pintype "passive"))
      (node (ref "C3") (pin "1") (pinfunction "1_1") (pintype "passive"))
      (node (ref "C38") (pin "1") (pinfunction "1_1") (pintype "passive"))
      (node (ref "C39") (pin "1") (pinfunction "1_1") (pintype "passive"))
      (node (ref "C4") (pin "1") (pinfunction "1_1") (pintype "passive"))
      (node (ref "C40") (pin "1") (pinfunction "1_1") (pintype "passive"))
      (node (ref "C41") (pin "1") (pinfunction "1_1") (pintype "passive"))
      (node (ref "C42") (pin "1") (pinfunction "1_1") (pintype "passive"))
      (node (ref "C43") (pin "1") (pinfunction "1_1") (pintype "passive"))
      (node (ref "C44") (pin "1") (pinfunction "1_1") (pintype "passive"))
      (node (ref "C45") (pin "1") (pinfunction "1_1") (pintype "passive"))
      (node (ref "C46") (pin "1") (pinfunction "1_1") (pintype "passive"))
      (node (ref "C47") (pin "1") (pinfunction "1_1") (pintype "passive"))
      (node (ref "C48") (pin "1") (pinfunction "1_1") (pintype "passive"))
      (node (ref "C49") (pin "1") (pinfunction "1_1") (pintype "passive"))
      (node (ref "C5") (pin "1") (pinfunction "1_1") (pintype "passive"))
      (node (ref "C50") (pin "1") (pinfunction "1_1") (pintype "passive"))
      (node (ref "C51") (pin "1") (pinfunction "1_1") (pintype "passive"))
      (node (ref "C52") (pin "1") (pinfunction "1_1") (pintype "passive"))
      (node (ref "C6") (pin "1") (pinfunction "1_1") (pintype "passive"))
      (node (ref "DS1") (pin "1") (pinfunction "GND_1") (pintype "passive"))
      (node (ref "J4") (pin "1") (pinfunction "1_1") (pintype "passive"))
      (node (ref "M1") (pin "1") (pinfunction "GND_1") (pintype "passive"))
      (node (ref "M1") (pin "37") (pinfunction "GND_37") (pintype "passive"))
      (node (ref "M1") (pin "38") (pinfunction "GND_38") (pintype "passive"))
      (node (ref "M1") (pin "4") (pinfunction "GND_4") (pintype "passive"))
      (node (ref "M1") (pin "40") (pinfunction "GND_40") (pintype "passive"))
      (node (ref "M1") (pin "41") (pinfunction "GND_41") (pintype "passive"))
      (node (ref "M1") (pin "62") (pinfunction "GND_62") (pintype "passive"))
      (node (ref "M1") (pin "63") (pinfunction "GND_63") (pintype "passive"))
      (node (ref "M1") (pin "64") (pinfunction "GND_64") (pintype "passive"))
      (node (ref "M1") (pin "65") (pinfunction "GND_65") (pintype "passive"))
      (node (ref "M1") (pin "66") (pinfunction "GND_66") (pintype "passive"))
      (node (ref "M1") (pin "67") (pinfunction "PADGND_67") (pintype "passive"))
      (node (ref "R2") (pin "2") (pinfunction "2_2") (pintype "passive"))
      (node (ref "R28") (pin "2") (pinfunction "2_2") (pintype "passive"))
      (node (ref "R29") (pin "2") (pinfunction "2_2") (pintype "passive"))
      (node (ref "R32") (pin "2") (pinfunction "2_2") (pintype "passive"))
      (node (ref "R33") (pin "2") (pinfunction "2_2") (pintype "passive"))
      (node (ref "R34") (pin "2") (pinfunction "2_2") (pintype "passive"))
      (node (ref "R5") (pin "2") (pinfunction "2_2") (pintype "passive"))
      (node (ref "U2") (pin "10") (pinfunction "PGND2_10") (pintype "passive"))
      (node (ref "U2") (pin "18") (pinfunction "GND_18") (pintype "passive"))
      (node (ref "U2") (pin "3") (pinfunction "PGND1_3") (pintype "passive"))
      (node (ref "U2") (pin "4") (pinfunction "PGND1_4") (pintype "passive"))
      (node (ref "U2") (pin "9") (pinfunction "PGND2_9") (pintype "passive"))
      (node (ref "U3") (pin "2") (pinfunction "GND_2") (pintype "passive"))
    )
    (net (code "51") (name "Net-(D1-K)") (class "Default")
      (node (ref "D1") (pin "1") (pinfunction "K_1") (pintype "passive"))
      (node (ref "R28") (pin "1") (pinfunction "1_1") (pintype "passive"))
    )
    (net (code "52") (name "Net-(D3-K)") (class "Default")
      (node (ref "D3") (pin "1") (pinfunction "K_1") (pintype "passive"))
      (node (ref "R33") (pin "1") (pinfunction "1_1") (pintype "passive"))
    )
    (net (code "53") (name "Net-(D4-K)") (class "Default")
      (node (ref "D4") (pin "1") (pinfunction "K_1") (pintype "passive"))
      (node (ref "R34") (pin "1") (pinfunction "1_1") (pintype "passive"))
    )
    (net (code "54") (name "Net-(M1-GPIO41_ADC0)") (class "Default")
      (node (ref "C38") (pin "2") (pinfunction "2_2") (pintype "passive"))
      (node (ref "M1") (pin "29") (pinfunction "GPIO41_ADC0_29") (pintype "passive"))
      (node (ref "R1") (pin "2") (pinfunction "2_2") (pintype "passive"))
      (node (ref "R2") (pin "1") (pinfunction "1_1") (pintype "passive"))
    )
    (net (code "55") (name "Net-(M1-PMU_EN)") (class "Default")
      (node (ref "M1") (pin "34") (pinfunction "PMU_EN_34") (pintype "passive"))
      (node (ref "R29") (pin "1") (pinfunction "1_1") (pintype "passive"))
    )
    (net (code "56") (name "Net-(M1-VOUT_2V5)") (class "Default")
      (node (ref "M1") (pin "32") (pinfunction "VOUT_2V5_32") (pintype "passive"))
      (node (ref "M1") (pin "33") (pinfunction "VREF_ADC_33") (pintype "passive"))
    )
    (net (code "57") (name "Net-(M1-WAKEUP)") (class "Default")
      (node (ref "M1") (pin "35") (pinfunction "WAKEUP_35") (pintype "passive"))
      (node (ref "R3") (pin "1") (pinfunction "1_1") (pintype "passive"))
    )
    (net (code "58") (name "Net-(U3-FB)") (class "Default")
      (node (ref "C19") (pin "1") (pinfunction "1_1") (pintype "passive"))
      (node (ref "R4") (pin "2") (pinfunction "2_2") (pintype "passive"))
      (node (ref "R5") (pin "1") (pinfunction "1_1") (pintype "passive"))
      (node (ref "U3") (pin "5") (pinfunction "FB_5") (pintype "passive"))
    )
    (net (code "59") (name "Net-(U3-SW)") (class "Default")
      (node (ref "L1") (pin "1") (pinfunction "1_1") (pintype "passive"))
      (node (ref "U3") (pin "3") (pinfunction "SW_3") (pintype "passive"))
    )
    (net (code "60") (name "VBAT") (class "Default")
      (node (ref "C18") (pin "2") (pinfunction "2_2") (pintype "passive"))
      (node (ref "C49") (pin "2") (pinfunction "2_2") (pintype "passive"))
      (node (ref "D1") (pin "2") (pinfunction "A_2") (pintype "passive"))
      (node (ref "L10") (pin "1") (pinfunction "1_1") (pintype "passive"))
      (node (ref "R1") (pin "1") (pinfunction "1_1") (pintype "passive"))
      (node (ref "SW1") (pin "3") (pinfunction "3_3") (pintype "passive"))
      (node (ref "U3") (pin "1") (pinfunction "EN_1") (pintype "passive"))
      (node (ref "U3") (pin "4") (pinfunction "VIN_4") (pintype "passive"))
    )
    (net (code "61") (name "unconnected-(J2-PadM1)") (class "Default")
      (node (ref "J2") (pin "M1") (pinfunction "M1_M1") (pintype "passive+no_connect"))
    )
    (net (code "62") (name "unconnected-(J2-PadM2)") (class "Default")
      (node (ref "J2") (pin "M2") (pinfunction "M2_M2") (pintype "passive+no_connect"))
    )
    (net (code "63") (name "unconnected-(J3-PadM1)") (class "Default")
      (node (ref "J3") (pin "M1") (pinfunction "M1_M1") (pintype "passive+no_connect"))
    )
    (net (code "64") (name "unconnected-(J3-PadM2)") (class "Default")
      (node (ref "J3") (pin "M2") (pinfunction "M2_M2") (pintype "passive+no_connect"))
    )
    (net (code "65") (name "unconnected-(J4-PadM1)") (class "Default")
      (node (ref "J4") (pin "M1") (pinfunction "M1_M1") (pintype "passive+no_connect"))
    )
    (net (code "66") (name "unconnected-(J4-PadM2)") (class "Default")
      (node (ref "J4") (pin "M2") (pinfunction "M2_M2") (pintype "passive+no_connect"))
    )
    (net (code "67") (name "unconnected-(M1-EXT_PMU_EN-Pad36)") (class "Default")
      (node (ref "M1") (pin "36") (pinfunction "EXT_PMU_EN_36") (pintype "passive+no_connect"))
    )
    (net (code "68") (name "unconnected-(M1-GPIO8_PWM8-Pad11)") (class "Default")
      (node (ref "M1") (pin "11") (pinfunction "GPIO8_PWM8_11") (pintype "passive+no_connect"))
    )
    (net (code "69") (name "unconnected-(M1-GPIO26_SCLK0_TXD0-Pad18)") (class "Default")
      (node (ref "M1") (pin "18") (pinfunction "GPIO26_SCLK0_TXD0_18") (pintype "passive+no_connect"))
    )
    (net (code "70") (name "unconnected-(M1-GPIO29_CSA0_CTS0-Pad21)") (class "Default")
      (node (ref "M1") (pin "21") (pinfunction "GPIO29_CSA0_CTS0_21") (pintype "passive+no_connect"))
    )
    (net (code "71") (name "unconnected-(M1-GPIO31_SCLK1_TXD1-Pad22)") (class "Default")
      (node (ref "M1") (pin "22") (pinfunction "GPIO31_SCLK1_TXD1_22") (pintype "passive+no_connect"))
    )
    (net (code "72") (name "unconnected-(M1-GPIO34_CSA1_CTS1-Pad25)") (class "Default")
      (node (ref "M1") (pin "25") (pinfunction "GPIO34_CSA1_CTS1_25") (pintype "passive+no_connect"))
    )
    (net (code "73") (name "unconnected-(M1-GPIO35_CSB1-Pad26)") (class "Default")
      (node (ref "M1") (pin "26") (pinfunction "GPIO35_CSB1_26") (pintype "passive+no_connect"))
    )
    (net (code "74") (name "unconnected-(M1-GPIO42_ADC1-Pad30)") (class "Default")
      (node (ref "M1") (pin "30") (pinfunction "GPIO42_ADC1_30") (pintype "passive+no_connect"))
    )
    (net (code "75") (name "unconnected-(M1-GPIO43_ADC2-Pad31)") (class "Default")
      (node (ref "M1") (pin "31") (pinfunction "GPIO43_ADC2_31") (pintype "passive+no_connect"))
    )
    (net (code "76") (name "unconnected-(M1-SWO-Pad50)") (class "Default")
      (node (ref "M1") (pin "50") (pinfunction "SWO_50") (pintype "passive+no_connect"))
    )
    (net (code "77") (name "unconnected-(SW1-Pad2)") (class "Default")
      (node (ref "SW1") (pin "2") (pinfunction "2_2") (pintype "passive"))
    )
  )
)
